# USB_BusinessCard.net
KiCad netlist of a schematic drawn in EAGLE
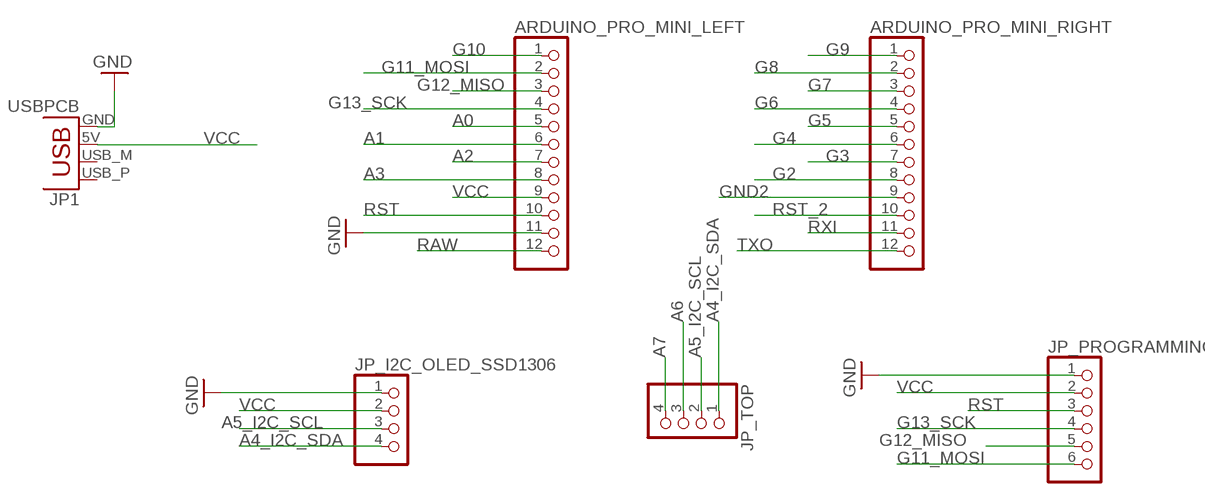
[diagram p0: schematic, sheet 1]

(export (version "E")
  (design (tool "Eeschema 10.0.6"))
  (components
    (comp (ref "ARDUINO_PRO_MINI_LEFT")
      (value "PINHD-1X12")
      (footprint "eagle-import:1X12")
      (libsource (lib "eagle-import") (part "PINHD-1X12"))
    )
    (comp (ref "ARDUINO_PRO_MINI_RIGHT")
      (value "PINHD-1X12")
      (footprint "eagle-import:1X12")
      (libsource (lib "eagle-import") (part "PINHD-1X12"))
    )
    (comp (ref "JP1")
      (value "USBPCB")
      (footprint "eagle-import:USB-A-PCB")
      (libsource (lib "eagle-import") (part "USBPCB"))
    )
    (comp (ref "JP_I2C_OLED_SSD1306")
      (value "PINHD-1X4")
      (footprint "eagle-import:1X04")
      (libsource (lib "eagle-import") (part "PINHD-1X4"))
    )
    (comp (ref "JP_PROGRAMMING")
      (value "PINHD-1X6")
      (footprint "eagle-import:1X06")
      (libsource (lib "eagle-import") (part "PINHD-1X6"))
    )
    (comp (ref "JP_TOP")
      (value "PINHD-1X4")
      (footprint "eagle-import:1X04")
      (libsource (lib "eagle-import") (part "PINHD-1X4"))
    )
  )
  (nets
    (net (code "1") (name "/A0") (class "Default")
      (node (ref "ARDUINO_PRO_MINI_LEFT") (pin "5") (pinfunction "5_5") (pintype "passive"))
    )
    (net (code "2") (name "/A1") (class "Default")
      (node (ref "ARDUINO_PRO_MINI_LEFT") (pin "6") (pinfunction "6_6") (pintype "passive"))
    )
    (net (code "3") (name "/A2") (class "Default")
      (node (ref "ARDUINO_PRO_MINI_LEFT") (pin "7") (pinfunction "7_7") (pintype "passive"))
    )
    (net (code "4") (name "/A3") (class "Default")
      (node (ref "ARDUINO_PRO_MINI_LEFT") (pin "8") (pinfunction "8_8") (pintype "passive"))
    )
    (net (code "5") (name "/A4_I2C_SDA") (class "Default")
      (node (ref "JP_I2C_OLED_SSD1306") (pin "4") (pinfunction "4_4") (pintype "passive"))
      (node (ref "JP_TOP") (pin "1") (pinfunction "1_1") (pintype "passive"))
    )
    (net (code "6") (name "/A5_I2C_SCL") (class "Default")
      (node (ref "JP_I2C_OLED_SSD1306") (pin "3") (pinfunction "3_3") (pintype "passive"))
      (node (ref "JP_TOP") (pin "2") (pinfunction "2_2") (pintype "passive"))
    )
    (net (code "7") (name "/A6") (class "Default")
      (node (ref "JP_TOP") (pin "3") (pinfunction "3_3") (pintype "passive"))
    )
    (net (code "8") (name "/A7") (class "Default")
      (node (ref "JP_TOP") (pin "4") (pinfunction "4_4") (pintype "passive"))
    )
    (net (code "9") (name "/G2") (class "Default")
      (node (ref "ARDUINO_PRO_MINI_RIGHT") (pin "8") (pinfunction "8_8") (pintype "passive"))
    )
    (net (code "10") (name "/G3") (class "Default")
      (node (ref "ARDUINO_PRO_MINI_RIGHT") (pin "7") (pinfunction "7_7") (pintype "passive"))
    )
    (net (code "11") (name "/G4") (class "Default")
      (node (ref "ARDUINO_PRO_MINI_RIGHT") (pin "6") (pinfunction "6_6") (pintype "passive"))
    )
    (net (code "12") (name "/G5") (class "Default")
      (node (ref "ARDUINO_PRO_MINI_RIGHT") (pin "5") (pinfunction "5_5") (pintype "passive"))
    )
    (net (code "13") (name "/G6") (class "Default")
      (node (ref "ARDUINO_PRO_MINI_RIGHT") (pin "4") (pinfunction "4_4") (pintype "passive"))
    )
    (net (code "14") (name "/G7") (class "Default")
      (node (ref "ARDUINO_PRO_MINI_RIGHT") (pin "3") (pinfunction "3_3") (pintype "passive"))
    )
    (net (code "15") (name "/G8") (class "Default")
      (node (ref "ARDUINO_PRO_MINI_RIGHT") (pin "2") (pinfunction "2_2") (pintype "passive"))
    )
    (net (code "16") (name "/G9") (class "Default")
      (node (ref "ARDUINO_PRO_MINI_RIGHT") (pin "1") (pinfunction "1_1") (pintype "passive"))
    )
    (net (code "17") (name "/G10") (class "Default")
      (node (ref "ARDUINO_PRO_MINI_LEFT") (pin "1") (pinfunction "1_1") (pintype "passive"))
    )
    (net (code "18") (name "/G11_MOSI") (class "Default")
      (node (ref "ARDUINO_PRO_MINI_LEFT") (pin "2") (pinfunction "2_2") (pintype "passive"))
      (node (ref "JP_PROGRAMMING") (pin "6") (pinfunction "6_6") (pintype "passive"))
    )
    (net (code "19") (name "/G12_MISO") (class "Default")
      (node (ref "ARDUINO_PRO_MINI_LEFT") (pin "3") (pinfunction "3_3") (pintype "passive"))
      (node (ref "JP_PROGRAMMING") (pin "5") (pinfunction "5_5") (pintype "passive"))
    )
    (net (code "20") (name "/G13_SCK") (class "Default")
      (node (ref "ARDUINO_PRO_MINI_LEFT") (pin "4") (pinfunction "4_4") (pintype "passive"))
      (node (ref "JP_PROGRAMMING") (pin "4") (pinfunction "4_4") (pintype "passive"))
    )
    (net (code "21") (name "/GND2") (class "Default")
      (node (ref "ARDUINO_PRO_MINI_RIGHT") (pin "9") (pinfunction "9_9") (pintype "passive"))
    )
    (net (code "22") (name "/RAW") (class "Default")
      (node (ref "ARDUINO_PRO_MINI_LEFT") (pin "12") (pinfunction "12_12") (pintype "passive"))
    )
    (net (code "23") (name "/RST") (class "Default")
      (node (ref "ARDUINO_PRO_MINI_LEFT") (pin "10") (pinfunction "10_10") (pintype "passive"))
      (node (ref "JP_PROGRAMMING") (pin "3") (pinfunction "3_3") (pintype "passive"))
    )
    (net (code "24") (name "/RST_2") (class "Default")
      (node (ref "ARDUINO_PRO_MINI_RIGHT") (pin "10") (pinfunction "10_10") (pintype "passive"))
    )
    (net (code "25") (name "/RXI") (class "Default")
      (node (ref "ARDUINO_PRO_MINI_RIGHT") (pin "11") (pinfunction "11_11") (pintype "passive"))
    )
    (net (code "26") (name "/TXO") (class "Default")
      (node (ref "ARDUINO_PRO_MINI_RIGHT") (pin "12") (pinfunction "12_12") (pintype "passive"))
    )
    (net (code "27") (name "/VCC") (class "Default")
      (node (ref "ARDUINO_PRO_MINI_LEFT") (pin "9") (pinfunction "9_9") (pintype "passive"))
      (node (ref "JP1") (pin "5V") (pinfunction "VBUS_5V") (pintype "bidirectional"))
      (node (ref "JP_I2C_OLED_SSD1306") (pin "2") (pinfunction "2_2") (pintype "passive"))
      (node (ref "JP_PROGRAMMING") (pin "2") (pinfunction "2_2") (pintype "passive"))
    )
    (net (code "28") (name "GND") (class "Default")
      (node (ref "ARDUINO_PRO_MINI_LEFT") (pin "11") (pinfunction "11_11") (pintype "passive"))
      (node (ref "JP1") (pin "GND") (pinfunction "GND_GND") (pintype "bidirectional"))
      (node (ref "JP_I2C_OLED_SSD1306") (pin "1") (pinfunction "1_1") (pintype "passive"))
      (node (ref "JP_PROGRAMMING") (pin "1") (pinfunction "1_1") (pintype "passive"))
    )
    (net (code "29") (name "unconnected-(JP1-D+-PadUSB_P)") (class "Default")
      (node (ref "JP1") (pin "USB_P") (pinfunction "D+_USB_P") (pintype "bidirectional"))
    )
    (net (code "30") (name "unconnected-(JP1-D--PadUSB_M)") (class "Default")
      (node (ref "JP1") (pin "USB_M") (pinfunction "D-_USB_M") (pintype "bidirectional"))
    )
  )
)
